# Sheet1.net
KiCad netlist of a schematic drawn in Altium Designer
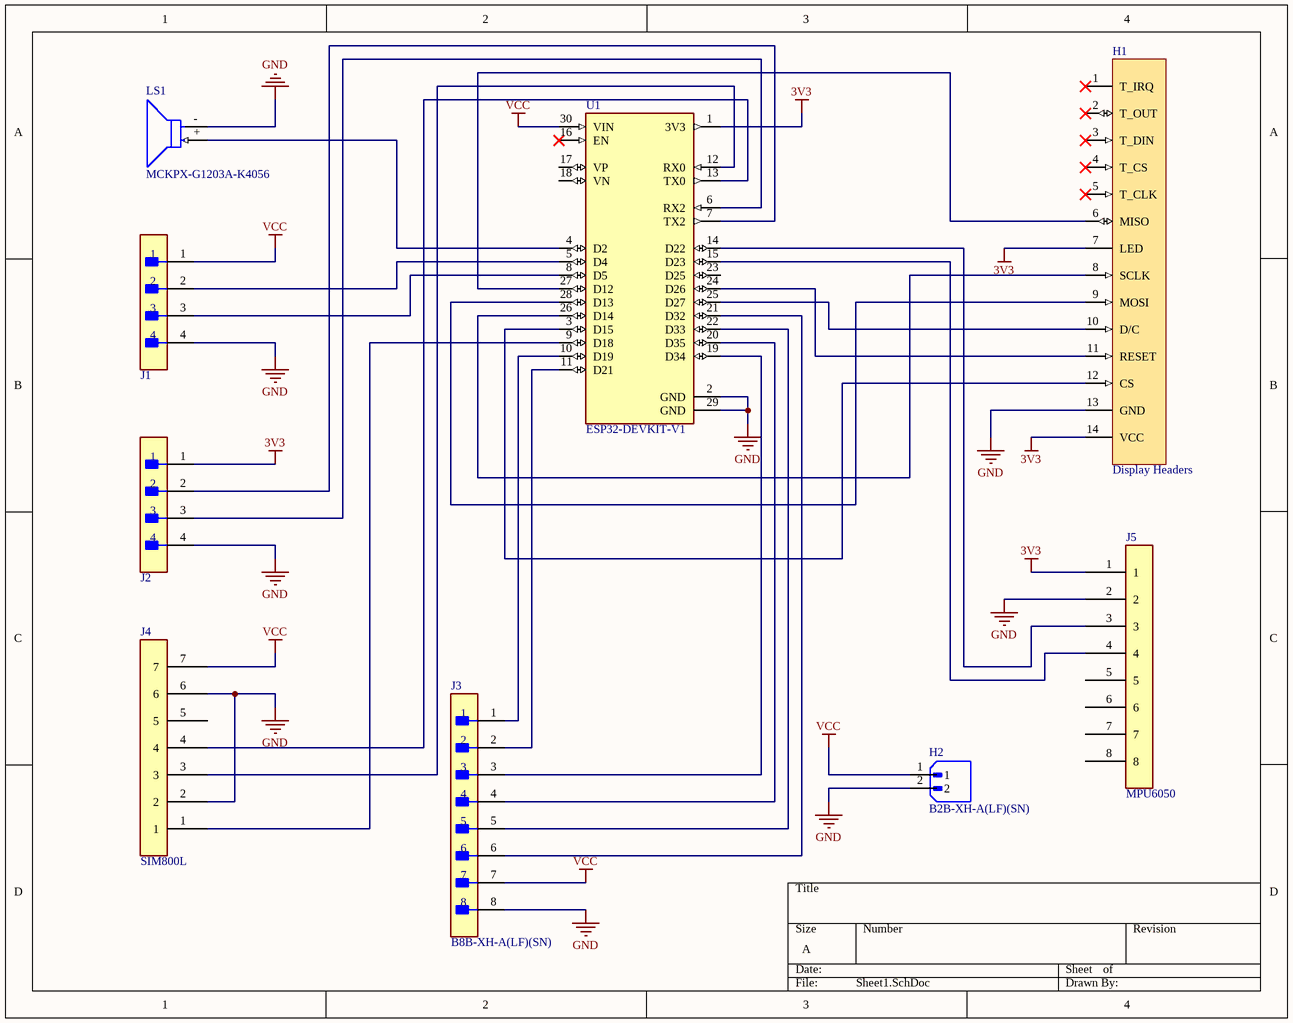
[diagram p0: Sheet1.SchDoc]

(export (version "E")
  (design (tool "Eeschema 10.0.6"))
  (components
    (comp (ref "H1")
      (value "Display Headers")
      (footprint "SULLINS_PPTC061LFBN-RC")
      (libsource (lib "Schlib1") (part "TFT-LCD-2.8'' Display Headers"))
    )
    (comp (ref "H2")
      (value "B2B-XH-A(LF)(SN)")
      (footprint "JST_B2B-XH-A(LF)(SN)")
      (description "Connector Header Through Hole 2 position 0.098 (2.50mm)")
      (fields (field (name "MF") "JST Sales America Inc."))
      (libsource (lib "Schlib1") (part "B2B-XH-A(LF)(SN)"))
    )
    (comp (ref "J1")
      (value "B04B-XASK-1(LF)(SN)")
      (footprint "FP-B04B-XASK-1_LF_SN-MFG")
      (description "CONN HEADER VERT 4POS 2.5MM")
      (fields
        (field (name "OCTOPART") "https://octopart.com/b04b-xask-1%28lf%29%28sn%29-jst-3990149")
        (field (name "MANUFACTURER") "JST")
      )
      (libsource (lib "Altium Content Vault") (part "299a8cea1bdcbc3624fe62c390fa72c"))
    )
    (comp (ref "J2")
      (value "GPS")
      (footprint "GPS")
      (fields
        (field (name "OCTOPART") "https://octopart.com/b04b-xask-1%28lf%29%28sn%29-jst-3990149")
        (field (name "MANUFACTURER PART NUMBER") "B04B-XASK-1(LF)(SN)")
        (field (name "MANUFACTURER") "JST")
      )
      (libsource (lib "Schlib1") (part "GPS"))
    )
    (comp (ref "J3")
      (value "B8B-XH-A(LF)(SN)")
      (footprint "FP-B8B-XH-A_LF_SN-MFG")
      (description "CONN HEADER VERT 8POS 2.5MM")
      (libsource (lib "Altium Content Vault") (part "99ec2b232beb5d2356d4d77f6a047f0"))
    )
    (comp (ref "J4") (value "SIM800L") (footprint "SIM800L") (libsource (lib "Schlib1") (part "SIM800L")))
    (comp (ref "J5") (value "MPU6050") (footprint "MPU6050") (libsource (lib "Schlib1") (part "MPU6050")))
    (comp (ref "LS1")
      (value "MCKPX-G1203A-K4056")
      (footprint "FP-MCKPX-G1203A-K4056-MFG - duplicate")
      (description "MAGNETIC BUZZER AND TRANSDUCER - More Details")
      (fields
        (field (name "MANUFACTURER") "Multicomp Pro")
        (field (name "OCTOPART") "https://octopart.com/mckpx-g1203a-k4056-multicomp-12157154")
      )
      (libsource (lib "Schlib1") (part "MCKPX-G1203A-K4056"))
    )
    (comp (ref "U1")
      (value "ESP32-DEVKIT-V1")
      (footprint "MODULE_ESP32_DEVKIT_V1")
      (fields (field (name "MF") "Do it"))
      (libsource (lib "Schlib1") (part "ESP32-DEVKIT-V1"))
    )
  )
  (nets
    (net (code "1") (name "3V3") (class "Default")
      (node (ref "H1") (pin "14") (pinfunction "VCC_14") (pintype "power_in"))
      (node (ref "H1") (pin "7") (pinfunction "LED_7") (pintype "power_in"))
      (node (ref "J2") (pin "1") (pinfunction "1_1") (pintype "passive"))
      (node (ref "J5") (pin "1") (pinfunction "1_1") (pintype "passive"))
      (node (ref "U1") (pin "1") (pinfunction "3V3_1") (pintype "output"))
    )
    (net (code "2") (name "GND") (class "Default")
      (node (ref "H1") (pin "13") (pinfunction "GND_13") (pintype "power_in"))
      (node (ref "H2") (pin "2") (pinfunction "2_2") (pintype "passive"))
      (node (ref "J1") (pin "4") (pinfunction "4_4") (pintype "passive"))
      (node (ref "J2") (pin "4") (pinfunction "4_4") (pintype "passive"))
      (node (ref "J3") (pin "8") (pinfunction "8_8") (pintype "passive"))
      (node (ref "J4") (pin "2") (pinfunction "2_2") (pintype "passive"))
      (node (ref "J4") (pin "6") (pinfunction "6_6") (pintype "passive"))
      (node (ref "J5") (pin "2") (pinfunction "2_2") (pintype "passive"))
      (node (ref "LS1") (pin "-") (pintype "power_in"))
      (node (ref "U1") (pin "2") (pinfunction "GND_2") (pintype "power_in"))
      (node (ref "U1") (pin "29") (pinfunction "GND_29") (pintype "power_in"))
    )
    (net (code "3") (name "Net-(H1-CS)") (class "Default")
      (node (ref "H1") (pin "12") (pinfunction "CS_12") (pintype "input"))
      (node (ref "U1") (pin "3") (pinfunction "D15_3") (pintype "bidirectional"))
    )
    (net (code "4") (name "Net-(H1-D{slash}C)") (class "Default")
      (node (ref "H1") (pin "10") (pinfunction "D/C_10") (pintype "input"))
      (node (ref "U1") (pin "25") (pinfunction "D27_25") (pintype "bidirectional"))
    )
    (net (code "5") (name "Net-(H1-MISO)") (class "Default")
      (node (ref "H1") (pin "6") (pinfunction "MISO_6") (pintype "bidirectional"))
      (node (ref "U1") (pin "27") (pinfunction "D12_27") (pintype "bidirectional"))
    )
    (net (code "6") (name "Net-(H1-MOSI)") (class "Default")
      (node (ref "H1") (pin "9") (pinfunction "MOSI_9") (pintype "input"))
      (node (ref "U1") (pin "28") (pinfunction "D13_28") (pintype "bidirectional"))
    )
    (net (code "7") (name "Net-(H1-RESET)") (class "Default")
      (node (ref "H1") (pin "11") (pinfunction "RESET_11") (pintype "input"))
      (node (ref "U1") (pin "24") (pinfunction "D26_24") (pintype "bidirectional"))
    )
    (net (code "8") (name "Net-(H1-SCLK)") (class "Default")
      (node (ref "H1") (pin "8") (pinfunction "SCLK_8") (pintype "input"))
      (node (ref "U1") (pin "26") (pinfunction "D14_26") (pintype "bidirectional"))
    )
    (net (code "9") (name "Net-(U1-D2)") (class "Default")
      (node (ref "LS1") (pin "+") (pinfunction "+_+") (pintype "input"))
      (node (ref "U1") (pin "4") (pinfunction "D2_4") (pintype "bidirectional"))
    )
    (net (code "10") (name "Net-(U1-D4)") (class "Default")
      (node (ref "J1") (pin "2") (pinfunction "2_2") (pintype "passive"))
      (node (ref "U1") (pin "5") (pinfunction "D4_5") (pintype "bidirectional"))
    )
    (net (code "11") (name "Net-(U1-D5)") (class "Default")
      (node (ref "J1") (pin "3") (pinfunction "3_3") (pintype "passive"))
      (node (ref "U1") (pin "8") (pinfunction "D5_8") (pintype "bidirectional"))
    )
    (net (code "12") (name "Net-(U1-D18)") (class "Default")
      (node (ref "J4") (pin "1") (pinfunction "1_1") (pintype "passive"))
      (node (ref "U1") (pin "9") (pinfunction "D18_9") (pintype "bidirectional"))
    )
    (net (code "13") (name "Net-(U1-D19)") (class "Default")
      (node (ref "J3") (pin "1") (pinfunction "1_1") (pintype "passive"))
      (node (ref "U1") (pin "10") (pinfunction "D19_10") (pintype "bidirectional"))
    )
    (net (code "14") (name "Net-(U1-D21)") (class "Default")
      (node (ref "J3") (pin "2") (pinfunction "2_2") (pintype "passive"))
      (node (ref "U1") (pin "11") (pinfunction "D21_11") (pintype "bidirectional"))
    )
    (net (code "15") (name "Net-(U1-D22)") (class "Default")
      (node (ref "J5") (pin "3") (pinfunction "3_3") (pintype "passive"))
      (node (ref "U1") (pin "14") (pinfunction "D22_14") (pintype "bidirectional"))
    )
    (net (code "16") (name "Net-(U1-D23)") (class "Default")
      (node (ref "J5") (pin "4") (pinfunction "4_4") (pintype "passive"))
      (node (ref "U1") (pin "15") (pinfunction "D23_15") (pintype "bidirectional"))
    )
    (net (code "17") (name "Net-(U1-D32)") (class "Default")
      (node (ref "J3") (pin "6") (pinfunction "6_6") (pintype "passive"))
      (node (ref "U1") (pin "21") (pinfunction "D32_21") (pintype "bidirectional"))
    )
    (net (code "18") (name "Net-(U1-D33)") (class "Default")
      (node (ref "J3") (pin "5") (pinfunction "5_5") (pintype "passive"))
      (node (ref "U1") (pin "22") (pinfunction "D33_22") (pintype "bidirectional"))
    )
    (net (code "19") (name "Net-(U1-D34)") (class "Default")
      (node (ref "J3") (pin "3") (pinfunction "3_3") (pintype "passive"))
      (node (ref "U1") (pin "19") (pinfunction "D34_19") (pintype "bidirectional"))
    )
    (net (code "20") (name "Net-(U1-D35)") (class "Default")
      (node (ref "J3") (pin "4") (pinfunction "4_4") (pintype "passive"))
      (node (ref "U1") (pin "20") (pinfunction "D35_20") (pintype "bidirectional"))
    )
    (net (code "21") (name "Net-(U1-RX0)") (class "Default")
      (node (ref "J4") (pin "3") (pinfunction "3_3") (pintype "passive"))
      (node (ref "U1") (pin "12") (pinfunction "RX0_12") (pintype "input"))
    )
    (net (code "22") (name "Net-(U1-RX2)") (class "Default")
      (node (ref "J2") (pin "3") (pinfunction "3_3") (pintype "passive"))
      (node (ref "U1") (pin "6") (pinfunction "RX2_6") (pintype "input"))
    )
    (net (code "23") (name "Net-(U1-TX0)") (class "Default")
      (node (ref "J4") (pin "4") (pinfunction "4_4") (pintype "passive"))
      (node (ref "U1") (pin "13") (pinfunction "TX0_13") (pintype "output"))
    )
    (net (code "24") (name "Net-(U1-TX2)") (class "Default")
      (node (ref "J2") (pin "2") (pinfunction "2_2") (pintype "passive"))
      (node (ref "U1") (pin "7") (pinfunction "TX2_7") (pintype "output"))
    )
    (net (code "25") (name "VCC") (class "Default")
      (node (ref "H2") (pin "1") (pinfunction "1_1") (pintype "passive"))
      (node (ref "J1") (pin "1") (pinfunction "1_1") (pintype "passive"))
      (node (ref "J3") (pin "7") (pinfunction "7_7") (pintype "passive"))
      (node (ref "J4") (pin "7") (pinfunction "7_7") (pintype "passive"))
      (node (ref "U1") (pin "30") (pinfunction "VIN_30") (pintype "input"))
    )
    (net (code "26") (name "unconnected-(H1-T_CLK-Pad5)") (class "Default")
      (node (ref "H1") (pin "5") (pinfunction "T_CLK_5") (pintype "input+no_connect"))
    )
    (net (code "27") (name "unconnected-(H1-T_CS-Pad4)") (class "Default")
      (node (ref "H1") (pin "4") (pinfunction "T_CS_4") (pintype "input+no_connect"))
    )
    (net (code "28") (name "unconnected-(H1-T_DIN-Pad3)") (class "Default")
      (node (ref "H1") (pin "3") (pinfunction "T_DIN_3") (pintype "input+no_connect"))
    )
    (net (code "29") (name "unconnected-(H1-T_IRQ-Pad1)") (class "Default")
      (node (ref "H1") (pin "1") (pinfunction "T_IRQ_1") (pintype "passive+no_connect"))
    )
    (net (code "30") (name "unconnected-(H1-T_OUT-Pad2)") (class "Default")
      (node (ref "H1") (pin "2") (pinfunction "T_OUT_2") (pintype "bidirectional+no_connect"))
    )
    (net (code "31") (name "unconnected-(J4-Pad5)") (class "Default")
      (node (ref "J4") (pin "5") (pinfunction "5_5") (pintype "passive"))
    )
    (net (code "32") (name "unconnected-(J5-Pad5)") (class "Default")
      (node (ref "J5") (pin "5") (pinfunction "5_5") (pintype "passive"))
    )
    (net (code "33") (name "unconnected-(J5-Pad6)") (class "Default")
      (node (ref "J5") (pin "6") (pinfunction "6_6") (pintype "passive"))
    )
    (net (code "34") (name "unconnected-(J5-Pad7)") (class "Default")
      (node (ref "J5") (pin "7") (pinfunction "7_7") (pintype "passive"))
    )
    (net (code "35") (name "unconnected-(J5-Pad8)") (class "Default")
      (node (ref "J5") (pin "8") (pinfunction "8_8") (pintype "passive"))
    )
    (net (code "36") (name "unconnected-(U1-D25-Pad23)") (class "Default")
      (node (ref "U1") (pin "23") (pinfunction "D25_23") (pintype "bidirectional"))
    )
    (net (code "37") (name "unconnected-(U1-EN-Pad16)") (class "Default")
      (node (ref "U1") (pin "16") (pinfunction "EN_16") (pintype "input+no_connect"))
    )
    (net (code "38") (name "unconnected-(U1-VN-Pad18)") (class "Default")
      (node (ref "U1") (pin "18") (pinfunction "VN_18") (pintype "bidirectional"))
    )
    (net (code "39") (name "unconnected-(U1-VP-Pad17)") (class "Default")
      (node (ref "U1") (pin "17") (pinfunction "VP_17") (pintype "bidirectional"))
    )
  )
)
